# Sheet1.net
KiCad netlist of a schematic drawn in Altium Designer
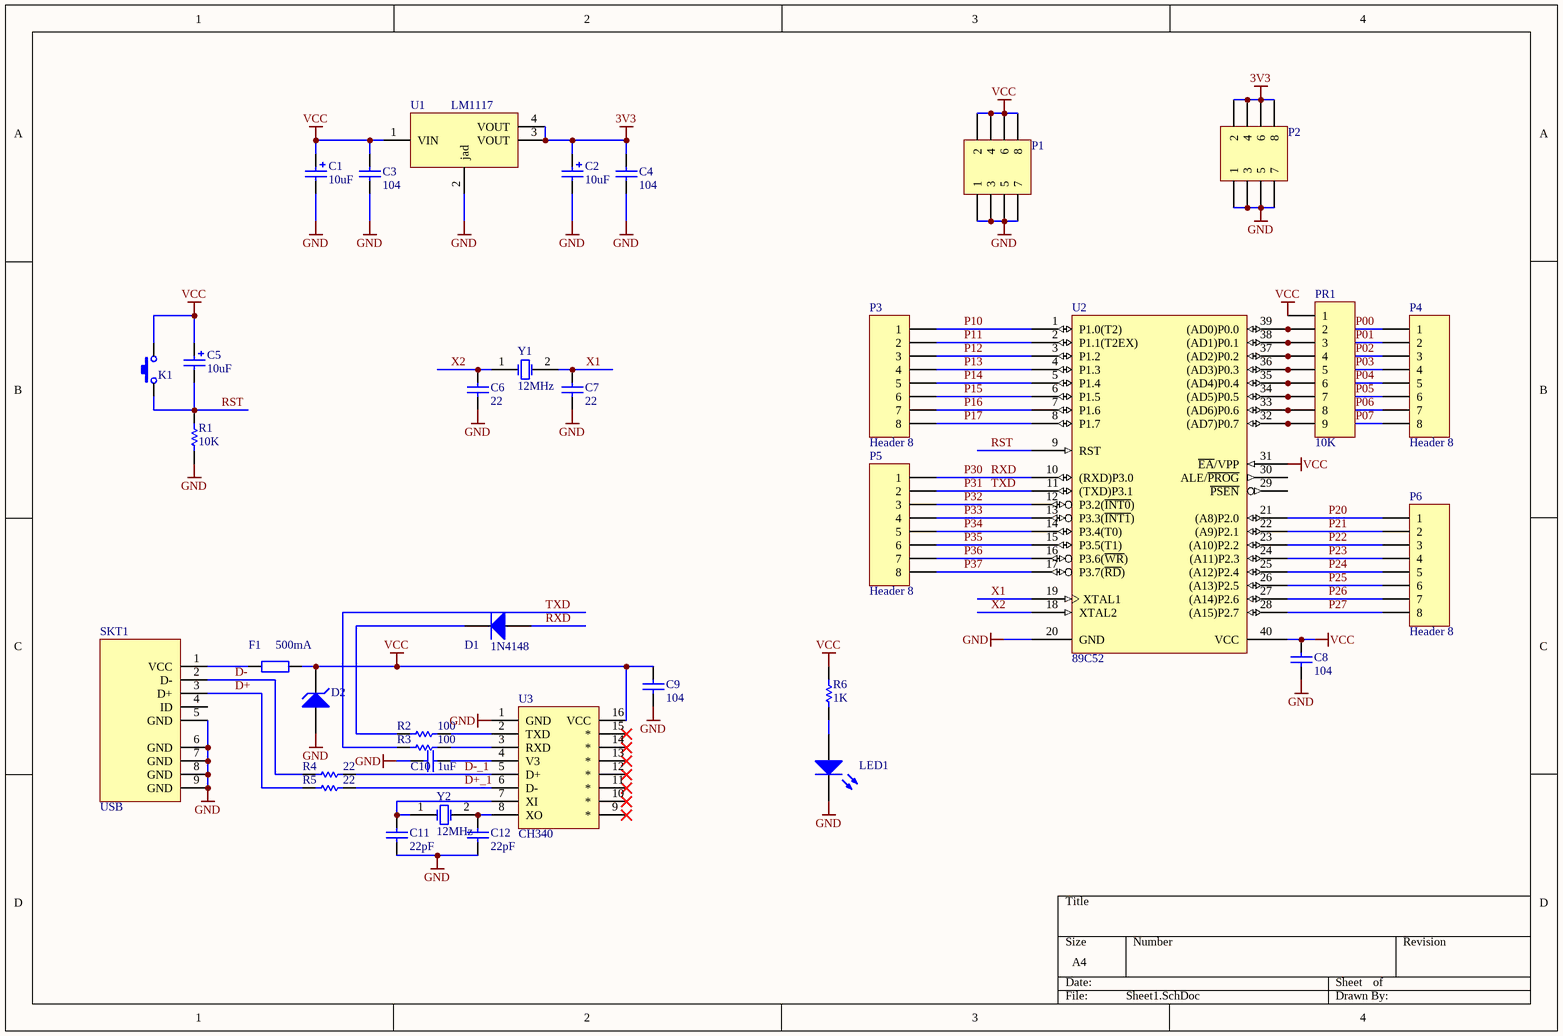
[diagram p0: Sheet1.SchDoc]

(export (version "E")
  (design (tool "Eeschema 10.0.6"))
  (components
    (comp (ref "C1")
      (value "10uF")
      (footprint "0805C")
      (description "Polarized Capacitor (Axial)")
      (fields (field (name "Comment") "Cap Pol2") (field (name "PUBLISHER") "Altium Limited"))
      (libsource (lib "Miscellaneous Devices") (part "Cap Pol2"))
    )
    (comp (ref "C2")
      (value "10uF")
      (footprint "0805C")
      (description "Polarized Capacitor (Axial)")
      (fields (field (name "Comment") "Cap Pol2") (field (name "PUBLISHER") "Altium Limited"))
      (libsource (lib "Miscellaneous Devices") (part "Cap Pol2"))
    )
    (comp (ref "C3")
      (value "104")
      (footprint "0805C")
      (description "Capacitor")
      (fields (field (name "Comment") "Cap") (field (name "PUBLISHER") "Altium Limited"))
      (libsource (lib "Miscellaneous Devices") (part "Cap"))
    )
    (comp (ref "C4")
      (value "104")
      (footprint "0805C")
      (description "Capacitor")
      (fields (field (name "Comment") "Cap") (field (name "PUBLISHER") "Altium Limited"))
      (libsource (lib "Miscellaneous Devices") (part "Cap"))
    )
    (comp (ref "C5")
      (value "10uF")
      (footprint "0805C")
      (description "Polarized Capacitor (Axial)")
      (fields (field (name "Comment") "Cap Pol2") (field (name "PUBLISHER") "Altium Limited"))
      (libsource (lib "Miscellaneous Devices") (part "Cap Pol2"))
    )
    (comp (ref "C6")
      (value "22")
      (footprint "0805C")
      (description "Capacitor")
      (fields (field (name "Comment") "Cap") (field (name "PUBLISHER") "Altium Limited"))
      (libsource (lib "Miscellaneous Devices") (part "Cap"))
    )
    (comp (ref "C7")
      (value "22")
      (footprint "0805C")
      (description "Capacitor")
      (fields (field (name "Comment") "Cap") (field (name "PUBLISHER") "Altium Limited"))
      (libsource (lib "Miscellaneous Devices") (part "Cap"))
    )
    (comp (ref "C8")
      (value "104")
      (footprint "0805C")
      (description "Capacitor")
      (fields (field (name "Comment") "Cap") (field (name "PUBLISHER") "Altium Limited"))
      (libsource (lib "Miscellaneous Devices") (part "Cap"))
    )
    (comp (ref "C9")
      (value "104")
      (footprint "0805C")
      (description "Capacitor")
      (fields (field (name "Comment") "Cap") (field (name "PUBLISHER") "Altium Limited"))
      (libsource (lib "Miscellaneous Devices") (part "Cap"))
    )
    (comp (ref "C10")
      (value "1uF")
      (footprint "0805C")
      (description "Capacitor")
      (fields (field (name "Comment") "Cap") (field (name "PUBLISHER") "Altium Limited"))
      (libsource (lib "Miscellaneous Devices") (part "Cap"))
    )
    (comp (ref "C11")
      (value "22pF")
      (footprint "0805C")
      (description "Capacitor")
      (fields (field (name "Comment") "Cap") (field (name "PUBLISHER") "Altium Limited"))
      (libsource (lib "Miscellaneous Devices") (part "Cap"))
    )
    (comp (ref "C12")
      (value "22pF")
      (footprint "0805C")
      (description "Capacitor")
      (fields (field (name "Comment") "Cap") (field (name "PUBLISHER") "Altium Limited"))
      (libsource (lib "Miscellaneous Devices") (part "Cap"))
    )
    (comp (ref "D1")
      (value "1N4148")
      (footprint "1206D")
      (description "High Conductance Fast Diode")
      (fields (field (name "PUBLISHER") "Altium Limited"))
      (libsource (lib "Miscellaneous Devices") (part "Diode 1N4148"))
    )
    (comp (ref "D2")
      (value "D Zener")
      (footprint "DO-214")
      (description "Zener Diode")
      (fields (field (name "PUBLISHER") "Altium Limited"))
      (libsource (lib "Miscellaneous Devices") (part "D Zener"))
    )
    (comp (ref "F1")
      (value "500mA")
      (footprint "0805R")
      (description "Resistor")
      (fields (field (name "Comment") "Res2") (field (name "PUBLISHER") "Altium Limited"))
      (libsource (lib "Miscellaneous Devices") (part "Res2"))
    )
    (comp (ref "K1") (value "SW") (footprint "IT-1187") (libsource (lib "自制元件库") (part "SW")))
    (comp (ref "LED1")
      (value "LED3")
      (footprint "LED0805G")
      (description "Typical BLUE SiC LED")
      (fields (field (name "PUBLISHER") "Altium Limited"))
      (libsource (lib "Miscellaneous Devices") (part "LED3"))
    )
    (comp (ref "P1")
      (value "Header 4X2")
      (footprint "HDR 2X4")
      (description "Header, 4-Pin, Dual row")
      (fields (field (name "PUBLISHER") "Altium Limited"))
      (libsource (lib "Miscellaneous Connectors") (part "Header 4X2"))
    )
    (comp (ref "P2")
      (value "Header 4X2")
      (footprint "HDR 2X4")
      (description "Header, 4-Pin, Dual row")
      (fields (field (name "PUBLISHER") "Altium Limited"))
      (libsource (lib "Miscellaneous Connectors") (part "Header 4X2"))
    )
    (comp (ref "P3")
      (value "Header 8")
      (footprint "HDR 1X8")
      (description "Header, 8-Pin")
      (fields (field (name "PUBLISHER") "Altium Limited"))
      (libsource (lib "Miscellaneous Connectors") (part "Header 8"))
    )
    (comp (ref "P4")
      (value "Header 8")
      (footprint "HDR 1X8")
      (description "Header, 8-Pin")
      (fields (field (name "PUBLISHER") "Altium Limited"))
      (libsource (lib "") (part "Header 8_1"))
    )
    (comp (ref "P5")
      (value "Header 8")
      (footprint "HDR 1X8")
      (description "Header, 8-Pin")
      (fields (field (name "PUBLISHER") "Altium Limited"))
      (libsource (lib "Miscellaneous Connectors") (part "Header 8"))
    )
    (comp (ref "P6")
      (value "Header 8")
      (footprint "HDR 1X8")
      (description "Header, 8-Pin")
      (fields (field (name "PUBLISHER") "Altium Limited"))
      (libsource (lib "") (part "Header 8_1"))
    )
    (comp (ref "PR1")
      (value "10K")
      (footprint "HDR1X9")
      (description "Header, 9-Pin")
      (fields (field (name "PUBLISHER") "Altium Limited"))
      (libsource (lib "Miscellaneous Connectors") (part "Header 9"))
    )
    (comp (ref "R1")
      (value "10K")
      (footprint "0805R")
      (description "Resistor")
      (fields (field (name "Comment") "Res1") (field (name "PUBLISHER") "Altium Limited"))
      (libsource (lib "Miscellaneous Devices") (part "Res1"))
    )
    (comp (ref "R2")
      (value "100")
      (footprint "0805R")
      (description "Resistor")
      (fields (field (name "Comment") "Res1") (field (name "PUBLISHER") "Altium Limited"))
      (libsource (lib "Miscellaneous Devices") (part "Res1"))
    )
    (comp (ref "R3")
      (value "100")
      (footprint "0805R")
      (description "Resistor")
      (fields (field (name "Comment") "Res1") (field (name "PUBLISHER") "Altium Limited"))
      (libsource (lib "Miscellaneous Devices") (part "Res1"))
    )
    (comp (ref "R4")
      (value "22")
      (footprint "0805R")
      (description "Resistor")
      (fields (field (name "Comment") "Res1") (field (name "PUBLISHER") "Altium Limited"))
      (libsource (lib "Miscellaneous Devices") (part "Res1"))
    )
    (comp (ref "R5")
      (value "22")
      (footprint "0805R")
      (description "Resistor")
      (fields (field (name "Comment") "Res1") (field (name "PUBLISHER") "Altium Limited"))
      (libsource (lib "Miscellaneous Devices") (part "Res1"))
    )
    (comp (ref "R6")
      (value "1K")
      (footprint "0805R")
      (description "Resistor")
      (fields (field (name "Comment") "Res1") (field (name "PUBLISHER") "Altium Limited"))
      (libsource (lib "Miscellaneous Devices") (part "Res1"))
    )
    (comp (ref "SKT1") (value "USB") (footprint "MicroUSB") (libsource (lib "自制元件库") (part "Micro USB")))
    (comp (ref "U1") (value "LM1117") (footprint "SOT_223") (libsource (lib "自制元件库") (part "1117")))
    (comp (ref "U2") (value "89C52") (footprint "DIP403D") (libsource (lib "自制元件库") (part "89C52")))
    (comp (ref "U3") (value "CH340") (footprint "SOIC-16") (libsource (lib "自制元件库") (part "CH340")))
    (comp (ref "Y1")
      (value "12MHz")
      (footprint "HC49")
      (description "Crystal Oscillator")
      (fields (field (name "PUBLISHER") "Altium Limited"))
      (libsource (lib "Miscellaneous Devices") (part "XTAL"))
    )
    (comp (ref "Y2")
      (value "12MHz")
      (footprint "HC49")
      (description "Crystal Oscillator")
      (fields (field (name "PUBLISHER") "Altium Limited"))
      (libsource (lib "Miscellaneous Devices") (part "XTAL"))
    )
  )
  (nets
    (net (code "1") (name "/D+") (class "Default")
      (node (ref "R5") (pin "1") (pinfunction "1_1") (pintype "passive"))
      (node (ref "SKT1") (pin "3") (pinfunction "D+_3") (pintype "passive"))
    )
    (net (code "2") (name "/D+_1") (class "Default")
      (node (ref "R5") (pin "2") (pinfunction "2_2") (pintype "passive"))
      (node (ref "U3") (pin "6") (pinfunction "D-_6") (pintype "passive"))
    )
    (net (code "3") (name "/D-") (class "Default")
      (node (ref "R4") (pin "1") (pinfunction "1_1") (pintype "passive"))
      (node (ref "SKT1") (pin "2") (pinfunction "D-_2") (pintype "passive"))
    )
    (net (code "4") (name "/D-_1") (class "Default")
      (node (ref "R4") (pin "2") (pinfunction "2_2") (pintype "passive"))
      (node (ref "U3") (pin "5") (pinfunction "D+_5") (pintype "passive"))
    )
    (net (code "5") (name "/P00") (class "Default")
      (node (ref "P4") (pin "1") (pinfunction "1_1") (pintype "passive"))
      (node (ref "PR1") (pin "2") (pinfunction "2_2") (pintype "passive"))
      (node (ref "U2") (pin "39") (pinfunction "(AD0)P0.0_39") (pintype "bidirectional"))
    )
    (net (code "6") (name "/P01") (class "Default")
      (node (ref "P4") (pin "2") (pinfunction "2_2") (pintype "passive"))
      (node (ref "PR1") (pin "3") (pinfunction "3_3") (pintype "passive"))
      (node (ref "U2") (pin "38") (pinfunction "(AD1)P0.1_38") (pintype "bidirectional"))
    )
    (net (code "7") (name "/P02") (class "Default")
      (node (ref "P4") (pin "3") (pinfunction "3_3") (pintype "passive"))
      (node (ref "PR1") (pin "4") (pinfunction "4_4") (pintype "passive"))
      (node (ref "U2") (pin "37") (pinfunction "(AD2)P0.2_37") (pintype "bidirectional"))
    )
    (net (code "8") (name "/P03") (class "Default")
      (node (ref "P4") (pin "4") (pinfunction "4_4") (pintype "passive"))
      (node (ref "PR1") (pin "5") (pinfunction "5_5") (pintype "passive"))
      (node (ref "U2") (pin "36") (pinfunction "(AD3)P0.3_36") (pintype "bidirectional"))
    )
    (net (code "9") (name "/P04") (class "Default")
      (node (ref "P4") (pin "5") (pinfunction "5_5") (pintype "passive"))
      (node (ref "PR1") (pin "6") (pinfunction "6_6") (pintype "passive"))
      (node (ref "U2") (pin "35") (pinfunction "(AD4)P0.4_35") (pintype "bidirectional"))
    )
    (net (code "10") (name "/P05") (class "Default")
      (node (ref "P4") (pin "6") (pinfunction "6_6") (pintype "passive"))
      (node (ref "PR1") (pin "7") (pinfunction "7_7") (pintype "passive"))
      (node (ref "U2") (pin "34") (pinfunction "(AD5)P0.5_34") (pintype "bidirectional"))
    )
    (net (code "11") (name "/P06") (class "Default")
      (node (ref "P4") (pin "7") (pinfunction "7_7") (pintype "passive"))
      (node (ref "PR1") (pin "8") (pinfunction "8_8") (pintype "passive"))
      (node (ref "U2") (pin "33") (pinfunction "(AD6)P0.6_33") (pintype "bidirectional"))
    )
    (net (code "12") (name "/P07") (class "Default")
      (node (ref "P4") (pin "8") (pinfunction "8_8") (pintype "passive"))
      (node (ref "PR1") (pin "9") (pinfunction "9_9") (pintype "passive"))
      (node (ref "U2") (pin "32") (pinfunction "(AD7)P0.7_32") (pintype "bidirectional"))
    )
    (net (code "13") (name "/P10") (class "Default")
      (node (ref "P3") (pin "1") (pinfunction "1_1") (pintype "passive"))
      (node (ref "U2") (pin "1") (pinfunction "P1.0(T2)_1") (pintype "bidirectional"))
    )
    (net (code "14") (name "/P11") (class "Default")
      (node (ref "P3") (pin "2") (pinfunction "2_2") (pintype "passive"))
      (node (ref "U2") (pin "2") (pinfunction "P1.1(T2EX)_2") (pintype "bidirectional"))
    )
    (net (code "15") (name "/P12") (class "Default")
      (node (ref "P3") (pin "3") (pinfunction "3_3") (pintype "passive"))
      (node (ref "U2") (pin "3") (pinfunction "P1.2_3") (pintype "bidirectional"))
    )
    (net (code "16") (name "/P13") (class "Default")
      (node (ref "P3") (pin "4") (pinfunction "4_4") (pintype "passive"))
      (node (ref "U2") (pin "4") (pinfunction "P1.3_4") (pintype "bidirectional"))
    )
    (net (code "17") (name "/P14") (class "Default")
      (node (ref "P3") (pin "5") (pinfunction "5_5") (pintype "passive"))
      (node (ref "U2") (pin "5") (pinfunction "P1.4_5") (pintype "bidirectional"))
    )
    (net (code "18") (name "/P15") (class "Default")
      (node (ref "P3") (pin "6") (pinfunction "6_6") (pintype "passive"))
      (node (ref "U2") (pin "6") (pinfunction "P1.5_6") (pintype "bidirectional"))
    )
    (net (code "19") (name "/P16") (class "Default")
      (node (ref "P3") (pin "7") (pinfunction "7_7") (pintype "passive"))
      (node (ref "U2") (pin "7") (pinfunction "P1.6_7") (pintype "bidirectional"))
    )
    (net (code "20") (name "/P17") (class "Default")
      (node (ref "P3") (pin "8") (pinfunction "8_8") (pintype "passive"))
      (node (ref "U2") (pin "8") (pinfunction "P1.7_8") (pintype "bidirectional"))
    )
    (net (code "21") (name "/P20") (class "Default")
      (node (ref "P6") (pin "1") (pinfunction "1_1") (pintype "passive"))
      (node (ref "U2") (pin "21") (pinfunction "(A8)P2.0_21") (pintype "bidirectional"))
    )
    (net (code "22") (name "/P21") (class "Default")
      (node (ref "P6") (pin "2") (pinfunction "2_2") (pintype "passive"))
      (node (ref "U2") (pin "22") (pinfunction "(A9)P2.1_22") (pintype "bidirectional"))
    )
    (net (code "23") (name "/P22") (class "Default")
      (node (ref "P6") (pin "3") (pinfunction "3_3") (pintype "passive"))
      (node (ref "U2") (pin "23") (pinfunction "(A10)P2.2_23") (pintype "bidirectional"))
    )
    (net (code "24") (name "/P23") (class "Default")
      (node (ref "P6") (pin "4") (pinfunction "4_4") (pintype "passive"))
      (node (ref "U2") (pin "24") (pinfunction "(A11)P2.3_24") (pintype "bidirectional"))
    )
    (net (code "25") (name "/P24") (class "Default")
      (node (ref "P6") (pin "5") (pinfunction "5_5") (pintype "passive"))
      (node (ref "U2") (pin "25") (pinfunction "(A12)P2.4_25") (pintype "bidirectional"))
    )
    (net (code "26") (name "/P25") (class "Default")
      (node (ref "P6") (pin "6") (pinfunction "6_6") (pintype "passive"))
      (node (ref "U2") (pin "26") (pinfunction "(A13)P2.5_26") (pintype "bidirectional"))
    )
    (net (code "27") (name "/P26") (class "Default")
      (node (ref "P6") (pin "7") (pinfunction "7_7") (pintype "passive"))
      (node (ref "U2") (pin "27") (pinfunction "(A14)P2.6_27") (pintype "bidirectional"))
    )
    (net (code "28") (name "/P27") (class "Default")
      (node (ref "P6") (pin "8") (pinfunction "8_8") (pintype "passive"))
      (node (ref "U2") (pin "28") (pinfunction "(A15)P2.7_28") (pintype "bidirectional"))
    )
    (net (code "29") (name "/P30") (class "Default")
      (node (ref "D1") (pin "1") (pinfunction "A_1") (pintype "passive"))
      (node (ref "P5") (pin "1") (pinfunction "1_1") (pintype "passive"))
      (node (ref "U2") (pin "10") (pinfunction "(RXD)P3.0_10") (pintype "bidirectional"))
    )
    (net (code "30") (name "/P31") (class "Default")
      (node (ref "P5") (pin "2") (pinfunction "2_2") (pintype "passive"))
      (node (ref "R3") (pin "1") (pinfunction "1_1") (pintype "passive"))
      (node (ref "U2") (pin "11") (pinfunction "(TXD)P3.1_11") (pintype "bidirectional"))
    )
    (net (code "31") (name "/P32") (class "Default")
      (node (ref "P5") (pin "3") (pinfunction "3_3") (pintype "passive"))
      (node (ref "U2") (pin "12") (pinfunction "P3.2(~{INT0})_12") (pintype "bidirectional"))
    )
    (net (code "32") (name "/P33") (class "Default")
      (node (ref "P5") (pin "4") (pinfunction "4_4") (pintype "passive"))
      (node (ref "U2") (pin "13") (pinfunction "P3.3(~{INT1})_13") (pintype "bidirectional"))
    )
    (net (code "33") (name "/P34") (class "Default")
      (node (ref "P5") (pin "5") (pinfunction "5_5") (pintype "passive"))
      (node (ref "U2") (pin "14") (pinfunction "P3.4(T0)_14") (pintype "bidirectional"))
    )
    (net (code "34") (name "/P35") (class "Default")
      (node (ref "P5") (pin "6") (pinfunction "6_6") (pintype "passive"))
      (node (ref "U2") (pin "15") (pinfunction "P3.5(T1)_15") (pintype "bidirectional"))
    )
    (net (code "35") (name "/P36") (class "Default")
      (node (ref "P5") (pin "7") (pinfunction "7_7") (pintype "passive"))
      (node (ref "U2") (pin "16") (pinfunction "P3.6(~{WR})_16") (pintype "bidirectional"))
    )
    (net (code "36") (name "/P37") (class "Default")
      (node (ref "P5") (pin "8") (pinfunction "8_8") (pintype "passive"))
      (node (ref "U2") (pin "17") (pinfunction "P3.7(~{RD})_17") (pintype "bidirectional"))
    )
    (net (code "37") (name "/RST") (class "Default")
      (node (ref "C5") (pin "2") (pinfunction "2_2") (pintype "passive"))
      (node (ref "K1") (pin "1") (pinfunction "1_1") (pintype "passive"))
      (node (ref "R1") (pin "2") (pinfunction "2_2") (pintype "passive"))
      (node (ref "U2") (pin "9") (pinfunction "RST_9") (pintype "input"))
    )
    (net (code "38") (name "/X1") (class "Default")
      (node (ref "C7") (pin "2") (pinfunction "2_2") (pintype "passive"))
      (node (ref "U2") (pin "19") (pinfunction "XTAL1_19") (pintype "input"))
      (node (ref "Y1") (pin "2") (pinfunction "OSC2_2") (pintype "passive"))
    )
    (net (code "39") (name "/X2") (class "Default")
      (node (ref "C6") (pin "2") (pinfunction "2_2") (pintype "passive"))
      (node (ref "U2") (pin "18") (pinfunction "XTAL2_18") (pintype "input"))
      (node (ref "Y1") (pin "1") (pinfunction "OSC1_1") (pintype "passive"))
    )
    (net (code "40") (name "3V3") (class "Default")
      (node (ref "C2") (pin "1") (pinfunction "1_1") (pintype "passive"))
      (node (ref "C4") (pin "2") (pinfunction "2_2") (pintype "passive"))
      (node (ref "P2") (pin "2") (pinfunction "2_2") (pintype "passive"))
      (node (ref "P2") (pin "4") (pinfunction "4_4") (pintype "passive"))
      (node (ref "P2") (pin "6") (pinfunction "6_6") (pintype "passive"))
      (node (ref "P2") (pin "8") (pinfunction "8_8") (pintype "passive"))
      (node (ref "U1") (pin "3") (pinfunction "VOUT_3") (pintype "passive"))
      (node (ref "U1") (pin "4") (pinfunction "VOUT_4") (pintype "passive"))
    )
    (net (code "41") (name "GND") (class "Default")
      (node (ref "C1") (pin "2") (pinfunction "2_2") (pintype "passive"))
      (node (ref "C10") (pin "2") (pinfunction "2_2") (pintype "passive"))
      (node (ref "C11") (pin "2") (pinfunction "2_2") (pintype "passive"))
      (node (ref "C12") (pin "2") (pinfunction "2_2") (pintype "passive"))
      (node (ref "C2") (pin "2") (pinfunction "2_2") (pintype "passive"))
      (node (ref "C3") (pin "1") (pinfunction "1_1") (pintype "passive"))
      (node (ref "C4") (pin "1") (pinfunction "1_1") (pintype "passive"))
      (node (ref "C6") (pin "1") (pinfunction "1_1") (pintype "passive"))
      (node (ref "C7") (pin "1") (pinfunction "1_1") (pintype "passive"))
      (node (ref "C8") (pin "1") (pinfunction "1_1") (pintype "passive"))
      (node (ref "C9") (pin "1") (pinfunction "1_1") (pintype "passive"))
      (node (ref "D2") (pin "1") (pinfunction "A_1") (pintype "passive"))
      (node (ref "LED1") (pin "2") (pinfunction "K_2") (pintype "passive"))
      (node (ref "P1") (pin "1") (pinfunction "1_1") (pintype "passive"))
      (node (ref "P1") (pin "3") (pinfunction "3_3") (pintype "passive"))
      (node (ref "P1") (pin "5") (pinfunction "5_5") (pintype "passive"))
      (node (ref "P1") (pin "7") (pinfunction "7_7") (pintype "passive"))
      (node (ref "P2") (pin "1") (pinfunction "1_1") (pintype "passive"))
      (node (ref "P2") (pin "3") (pinfunction "3_3") (pintype "passive"))
      (node (ref "P2") (pin "5") (pinfunction "5_5") (pintype "passive"))
      (node (ref "P2") (pin "7") (pinfunction "7_7") (pintype "passive"))
      (node (ref "R1") (pin "1") (pinfunction "1_1") (pintype "passive"))
      (node (ref "SKT1") (pin "5") (pinfunction "GND_5") (pintype "passive"))
      (node (ref "SKT1") (pin "6") (pinfunction "GND_6") (pintype "passive"))
      (node (ref "SKT1") (pin "7") (pinfunction "GND_7") (pintype "passive"))
      (node (ref "SKT1") (pin "8") (pinfunction "GND_8") (pintype "passive"))
      (node (ref "SKT1") (pin "9") (pinfunction "GND_9") (pintype "passive"))
      (node (ref "U1") (pin "2") (pinfunction "jad_2") (pintype "passive"))
      (node (ref "U2") (pin "20") (pinfunction "GND_20") (pintype "power_in"))
      (node (ref "U3") (pin "1") (pinfunction "GND_1") (pintype "passive"))
    )
    (net (code "42") (name "Net-(D1-K)") (class "Default")
      (node (ref "D1") (pin "2") (pinfunction "K_2") (pintype "passive"))
      (node (ref "R2") (pin "1") (pinfunction "1_1") (pintype "passive"))
    )
    (net (code "43") (name "Net-(LED1-A)") (class "Default")
      (node (ref "LED1") (pin "1") (pinfunction "A_1") (pintype "passive"))
      (node (ref "R6") (pin "1") (pinfunction "1_1") (pintype "passive"))
    )
    (net (code "44") (name "Net-(SKT1-VCC)") (class "Default")
      (node (ref "F1") (pin "1") (pinfunction "1_1") (pintype "passive"))
      (node (ref "SKT1") (pin "1") (pinfunction "VCC_1") (pintype "passive"))
    )
    (net (code "45") (name "Net-(U3-RXD)") (class "Default")
      (node (ref "R3") (pin "2") (pinfunction "2_2") (pintype "passive"))
      (node (ref "U3") (pin "3") (pinfunction "RXD_3") (pintype "passive"))
    )
    (net (code "46") (name "Net-(U3-TXD)") (class "Default")
      (node (ref "R2") (pin "2") (pinfunction "2_2") (pintype "passive"))
      (node (ref "U3") (pin "2") (pinfunction "TXD_2") (pintype "passive"))
    )
    (net (code "47") (name "Net-(U3-V3)") (class "Default")
      (node (ref "C10") (pin "1") (pinfunction "1_1") (pintype "passive"))
      (node (ref "U3") (pin "4") (pinfunction "V3_4") (pintype "passive"))
    )
    (net (code "48") (name "Net-(U3-XI)") (class "Default")
      (node (ref "C11") (pin "1") (pinfunction "1_1") (pintype "passive"))
      (node (ref "U3") (pin "7") (pinfunction "XI_7") (pintype "passive"))
      (node (ref "Y2") (pin "1") (pinfunction "OSC1_1") (pintype "passive"))
    )
    (net (code "49") (name "Net-(U3-XO)") (class "Default")
      (node (ref "C12") (pin "1") (pinfunction "1_1") (pintype "passive"))
      (node (ref "U3") (pin "8") (pinfunction "XO_8") (pintype "passive"))
      (node (ref "Y2") (pin "2") (pinfunction "OSC2_2") (pintype "passive"))
    )
    (net (code "50") (name "VCC") (class "Default")
      (node (ref "C1") (pin "1") (pinfunction "1_1") (pintype "passive"))
      (node (ref "C3") (pin "2") (pinfunction "2_2") (pintype "passive"))
      (node (ref "C5") (pin "1") (pinfunction "1_1") (pintype "passive"))
      (node (ref "C8") (pin "2") (pinfunction "2_2") (pintype "passive"))
      (node (ref "C9") (pin "2") (pinfunction "2_2") (pintype "passive"))
      (node (ref "D2") (pin "2") (pinfunction "K_2") (pintype "passive"))
      (node (ref "F1") (pin "2") (pinfunction "2_2") (pintype "passive"))
      (node (ref "K1") (pin "2") (pinfunction "2_2") (pintype "passive"))
      (node (ref "P1") (pin "2") (pinfunction "2_2") (pintype "passive"))
      (node (ref "P1") (pin "4") (pinfunction "4_4") (pintype "passive"))
      (node (ref "P1") (pin "6") (pinfunction "6_6") (pintype "passive"))
      (node (ref "P1") (pin "8") (pinfunction "8_8") (pintype "passive"))
      (node (ref "PR1") (pin "1") (pinfunction "1_1") (pintype "passive"))
      (node (ref "R6") (pin "2") (pinfunction "2_2") (pintype "passive"))
      (node (ref "U1") (pin "1") (pinfunction "VIN_1") (pintype "passive"))
      (node (ref "U2") (pin "31") (pinfunction "~{EA}/VPP_31") (pintype "input"))
      (node (ref "U2") (pin "40") (pinfunction "VCC_40") (pintype "power_in"))
      (node (ref "U3") (pin "16") (pinfunction "VCC_16") (pintype "passive"))
    )
    (net (code "51") (name "unconnected-(SKT1-ID-Pad4)") (class "Default")
      (node (ref "SKT1") (pin "4") (pinfunction "ID_4") (pintype "passive"))
    )
    (net (code "52") (name "unconnected-(U2-ALE{slash}~{PROG}-Pad30)") (class "Default")
      (node (ref "U2") (pin "30") (pinfunction "ALE/~{PROG}_30") (pintype "output"))
    )
    (net (code "53") (name "unconnected-(U2-~{PSEN}-Pad29)") (class "Default")
      (node (ref "U2") (pin "29") (pinfunction "~{PSEN}_29") (pintype "output"))
    )
    (net (code "54") (name "unconnected-(U3-*-Pad9)") (class "Default")
      (node (ref "U3") (pin "9") (pinfunction "*_9") (pintype "passive+no_connect"))
    )
    (net (code "55") (name "unconnected-(U3-*-Pad10)") (class "Default")
      (node (ref "U3") (pin "10") (pinfunction "*_10") (pintype "passive+no_connect"))
    )
    (net (code "56") (name "unconnected-(U3-*-Pad11)") (class "Default")
      (node (ref "U3") (pin "11") (pinfunction "*_11") (pintype "passive+no_connect"))
    )
    (net (code "57") (name "unconnected-(U3-*-Pad12)") (class "Default")
      (node (ref "U3") (pin "12") (pinfunction "*_12") (pintype "passive+no_connect"))
    )
    (net (code "58") (name "unconnected-(U3-*-Pad13)") (class "Default")
      (node (ref "U3") (pin "13") (pinfunction "*_13") (pintype "passive+no_connect"))
    )
    (net (code "59") (name "unconnected-(U3-*-Pad14)") (class "Default")
      (node (ref "U3") (pin "14") (pinfunction "*_14") (pintype "passive+no_connect"))
    )
    (net (code "60") (name "unconnected-(U3-*-Pad15)") (class "Default")
      (node (ref "U3") (pin "15") (pinfunction "*_15") (pintype "passive+no_connect"))
    )
  )
)
